# main-v4.net
KiCad netlist of a schematic drawn in EAGLE
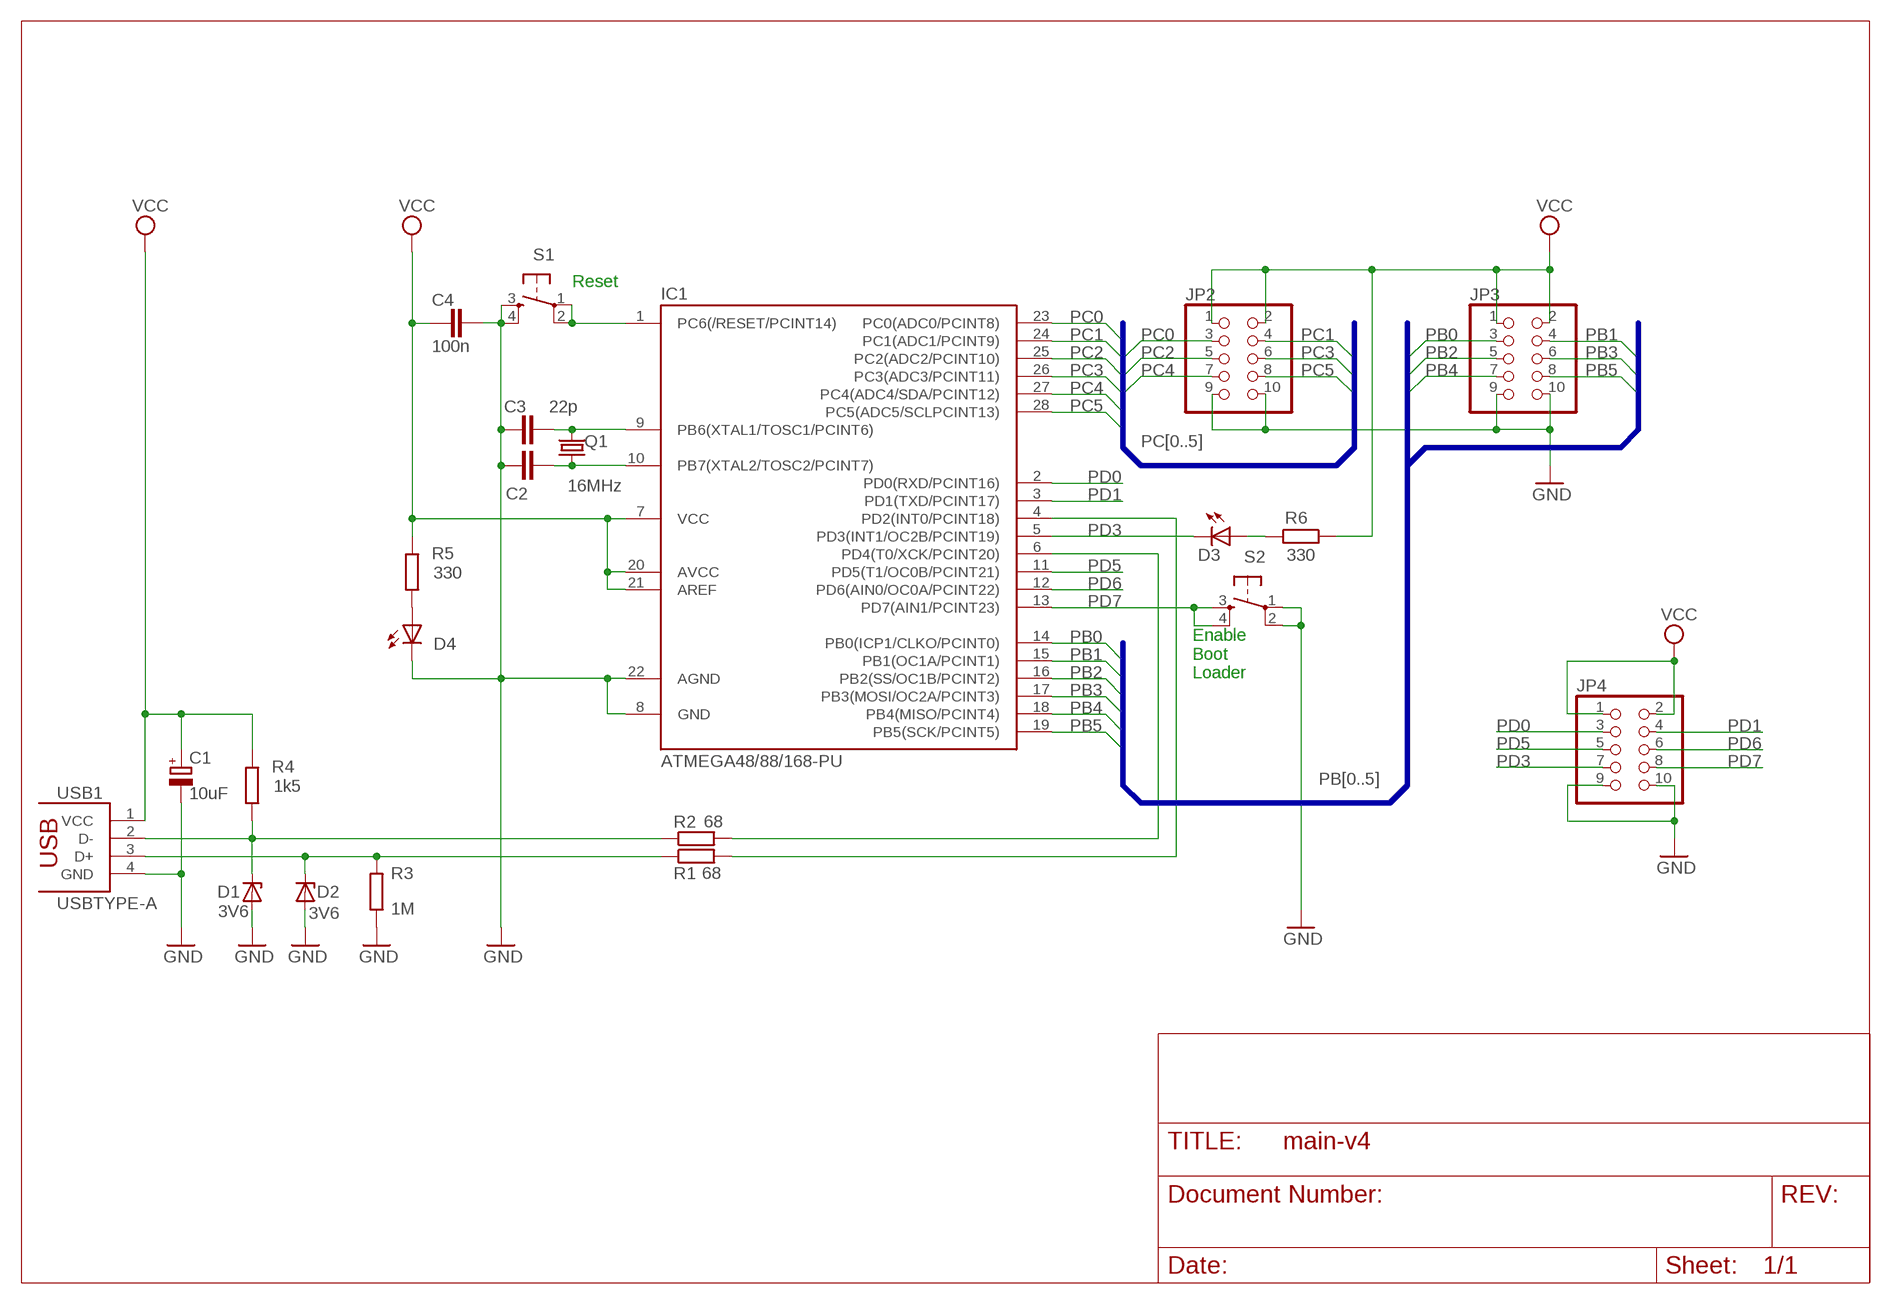
[diagram p0: schematic, sheet 1]

(export (version "E")
  (design (tool "Eeschema 10.0.6"))
  (components
    (comp (ref "C1")
      (value "10uF")
      (footprint "eagle-import:E2,5-6E")
      (libsource (lib "eagle-import") (part "CPOL-EUE2,5-6E"))
    )
    (comp (ref "C2")
      (value "22p")
      (footprint "eagle-import:C025-024X044")
      (libsource (lib "eagle-import") (part "C-EU025-024X044"))
    )
    (comp (ref "C3")
      (value "22p")
      (footprint "eagle-import:C025-024X044")
      (libsource (lib "eagle-import") (part "C-EU025-024X044"))
    )
    (comp (ref "C4")
      (value "100n")
      (footprint "eagle-import:C050-024X044")
      (libsource (lib "eagle-import") (part "C-EU050-024X044"))
    )
    (comp (ref "D1")
      (value "3V6")
      (footprint "eagle-import:DO34Z7")
      (libsource (lib "eagle-import") (part "ZENER-DIODEDO34-7"))
    )
    (comp (ref "D2")
      (value "3V6")
      (footprint "eagle-import:DO34Z7")
      (libsource (lib "eagle-import") (part "ZENER-DIODEDO34-7"))
    )
    (comp (ref "D3")
      (value "LED3MM")
      (footprint "eagle-import:LED3MM")
      (libsource (lib "eagle-import") (part "LED3MM"))
    )
    (comp (ref "D4")
      (value "LED3MM")
      (footprint "eagle-import:LED3MM")
      (libsource (lib "eagle-import") (part "LED3MM"))
    )
    (comp (ref "IC1")
      (value "ATMEGA48/88/168-PU")
      (footprint "eagle-import:DIL28-3")
      (libsource (lib "eagle-import") (part "ATMEGA48/88/168-PU"))
    )
    (comp (ref "JP2")
      (value "HEADER-2X5")
      (footprint "eagle-import:2X05")
      (libsource (lib "eagle-import") (part "HEADER-2X5"))
    )
    (comp (ref "JP3")
      (value "HEADER-2X5")
      (footprint "eagle-import:2X05")
      (libsource (lib "eagle-import") (part "HEADER-2X5"))
    )
    (comp (ref "JP4")
      (value "HEADER-2X5")
      (footprint "eagle-import:2X05")
      (libsource (lib "eagle-import") (part "HEADER-2X5"))
    )
    (comp (ref "Q1")
      (value "16MHz")
      (footprint "eagle-import:HC49_S")
      (libsource (lib "eagle-import") (part "CRYSTALHC49S"))
    )
    (comp (ref "R1")
      (value "68")
      (footprint "eagle-import:0207_10")
      (libsource (lib "eagle-import") (part "R-EU_0207/10"))
    )
    (comp (ref "R2")
      (value "68")
      (footprint "eagle-import:0207_10")
      (libsource (lib "eagle-import") (part "R-EU_0207/10"))
    )
    (comp (ref "R3")
      (value "1M")
      (footprint "eagle-import:0207_10")
      (libsource (lib "eagle-import") (part "R-EU_0207/10"))
    )
    (comp (ref "R4")
      (value "1k5")
      (footprint "eagle-import:0207_10")
      (libsource (lib "eagle-import") (part "R-EU_0207/10"))
    )
    (comp (ref "R5")
      (value "330")
      (footprint "eagle-import:0207_10")
      (libsource (lib "eagle-import") (part "R-EU_0207/10"))
    )
    (comp (ref "R6")
      (value "330")
      (footprint "eagle-import:0207_10")
      (libsource (lib "eagle-import") (part "R-EU_0207/10"))
    )
    (comp (ref "S1")
      (value "DTS-6")
      (footprint "eagle-import:DTS-6")
      (libsource (lib "eagle-import") (part "DTS-6"))
    )
    (comp (ref "S2")
      (value "DTS-6")
      (footprint "eagle-import:DTS-6")
      (libsource (lib "eagle-import") (part "DTS-6"))
    )
    (comp (ref "USB1")
      (value "USBTYPE-A")
      (footprint "eagle-import:USBTYPE-A")
      (libsource (lib "eagle-import") (part "USBTYPE-A"))
    )
  )
  (nets
    (net (code "1") (name "/PB0") (class "Default")
      (node (ref "IC1") (pin "14") (pinfunction "PB0(ICP1/CLKO/PCINT0)_14") (pintype "bidirectional"))
      (node (ref "JP3") (pin "3") (pinfunction "3_3") (pintype "passive"))
    )
    (net (code "2") (name "/PB1") (class "Default")
      (node (ref "IC1") (pin "15") (pinfunction "PB1(OC1A/PCINT1)_15") (pintype "bidirectional"))
      (node (ref "JP3") (pin "4") (pinfunction "4_4") (pintype "passive"))
    )
    (net (code "3") (name "/PB2") (class "Default")
      (node (ref "IC1") (pin "16") (pinfunction "PB2(SS/OC1B/PCINT2)_16") (pintype "bidirectional"))
      (node (ref "JP3") (pin "5") (pinfunction "5_5") (pintype "passive"))
    )
    (net (code "4") (name "/PB3") (class "Default")
      (node (ref "IC1") (pin "17") (pinfunction "PB3(MOSI/OC2A/PCINT3)_17") (pintype "bidirectional"))
      (node (ref "JP3") (pin "6") (pinfunction "6_6") (pintype "passive"))
    )
    (net (code "5") (name "/PB4") (class "Default")
      (node (ref "IC1") (pin "18") (pinfunction "PB4(MISO/PCINT4)_18") (pintype "bidirectional"))
      (node (ref "JP3") (pin "7") (pinfunction "7_7") (pintype "passive"))
    )
    (net (code "6") (name "/PB5") (class "Default")
      (node (ref "IC1") (pin "19") (pinfunction "PB5(SCK/PCINT5)_19") (pintype "bidirectional"))
      (node (ref "JP3") (pin "8") (pinfunction "8_8") (pintype "passive"))
    )
    (net (code "8") (name "/PC0") (class "Default")
      (node (ref "IC1") (pin "23") (pinfunction "PC0(ADC0/PCINT8)_23") (pintype "bidirectional"))
      (node (ref "JP2") (pin "3") (pinfunction "3_3") (pintype "passive"))
    )
    (net (code "9") (name "/PC1") (class "Default")
      (node (ref "IC1") (pin "24") (pinfunction "PC1(ADC1/PCINT9)_24") (pintype "bidirectional"))
      (node (ref "JP2") (pin "4") (pinfunction "4_4") (pintype "passive"))
    )
    (net (code "10") (name "/PC2") (class "Default")
      (node (ref "IC1") (pin "25") (pinfunction "PC2(ADC2/PCINT10)_25") (pintype "bidirectional"))
      (node (ref "JP2") (pin "5") (pinfunction "5_5") (pintype "passive"))
    )
    (net (code "11") (name "/PC3") (class "Default")
      (node (ref "IC1") (pin "26") (pinfunction "PC3(ADC3/PCINT11)_26") (pintype "bidirectional"))
      (node (ref "JP2") (pin "6") (pinfunction "6_6") (pintype "passive"))
    )
    (net (code "12") (name "/PC4") (class "Default")
      (node (ref "IC1") (pin "27") (pinfunction "PC4(ADC4/SDA/PCINT12)_27") (pintype "bidirectional"))
      (node (ref "JP2") (pin "7") (pinfunction "7_7") (pintype "passive"))
    )
    (net (code "13") (name "/PC5") (class "Default")
      (node (ref "IC1") (pin "28") (pinfunction "PC5(ADC5/SCLPCINT13)_28") (pintype "bidirectional"))
      (node (ref "JP2") (pin "8") (pinfunction "8_8") (pintype "passive"))
    )
    (net (code "15") (name "/PD0") (class "Default")
      (node (ref "IC1") (pin "2") (pinfunction "PD0(RXD/PCINT16)_2") (pintype "bidirectional"))
      (node (ref "JP4") (pin "3") (pinfunction "3_3") (pintype "passive"))
    )
    (net (code "16") (name "/PD1") (class "Default")
      (node (ref "IC1") (pin "3") (pinfunction "PD1(TXD/PCINT17)_3") (pintype "bidirectional"))
      (node (ref "JP4") (pin "4") (pinfunction "4_4") (pintype "passive"))
    )
    (net (code "17") (name "/PD3") (class "Default")
      (node (ref "D3") (pin "K") (pinfunction "C_K") (pintype "passive"))
      (node (ref "IC1") (pin "5") (pinfunction "PD3(INT1/OC2B/PCINT19)_5") (pintype "bidirectional"))
      (node (ref "JP4") (pin "7") (pinfunction "7_7") (pintype "passive"))
    )
    (net (code "18") (name "/PD5") (class "Default")
      (node (ref "IC1") (pin "11") (pinfunction "PD5(T1/OC0B/PCINT21)_11") (pintype "bidirectional"))
      (node (ref "JP4") (pin "5") (pinfunction "5_5") (pintype "passive"))
    )
    (net (code "19") (name "/PD6") (class "Default")
      (node (ref "IC1") (pin "12") (pinfunction "PD6(AIN0/OC0A/PCINT22)_12") (pintype "bidirectional"))
      (node (ref "JP4") (pin "6") (pinfunction "6_6") (pintype "passive"))
    )
    (net (code "20") (name "/PD7") (class "Default")
      (node (ref "IC1") (pin "13") (pinfunction "PD7(AIN1/PCINT23)_13") (pintype "bidirectional"))
      (node (ref "JP4") (pin "8") (pinfunction "8_8") (pintype "passive"))
      (node (ref "S2") (pin "3") (pinfunction "3_3") (pintype "passive"))
      (node (ref "S2") (pin "4") (pinfunction "4_4") (pintype "passive"))
    )
    (net (code "21") (name "GND") (class "Default")
      (node (ref "C1") (pin "-") (pinfunction "-_-") (pintype "passive"))
      (node (ref "C2") (pin "1") (pinfunction "1_1") (pintype "passive"))
      (node (ref "C3") (pin "1") (pinfunction "1_1") (pintype "passive"))
      (node (ref "C4") (pin "2") (pinfunction "2_2") (pintype "passive"))
      (node (ref "D1") (pin "A") (pinfunction "A_A") (pintype "passive"))
      (node (ref "D2") (pin "A") (pinfunction "A_A") (pintype "passive"))
      (node (ref "D4") (pin "K") (pinfunction "C_K") (pintype "passive"))
      (node (ref "IC1") (pin "22") (pinfunction "AGND_22") (pintype "power_in"))
      (node (ref "IC1") (pin "8") (pinfunction "GND_8") (pintype "power_in"))
      (node (ref "JP2") (pin "10") (pinfunction "10_10") (pintype "passive"))
      (node (ref "JP2") (pin "9") (pinfunction "9_9") (pintype "passive"))
      (node (ref "JP3") (pin "10") (pinfunction "10_10") (pintype "passive"))
      (node (ref "JP3") (pin "9") (pinfunction "9_9") (pintype "passive"))
      (node (ref "JP4") (pin "10") (pinfunction "10_10") (pintype "passive"))
      (node (ref "JP4") (pin "9") (pinfunction "9_9") (pintype "passive"))
      (node (ref "R3") (pin "1") (pinfunction "1_1") (pintype "passive"))
      (node (ref "S1") (pin "3") (pinfunction "3_3") (pintype "passive"))
      (node (ref "S1") (pin "4") (pinfunction "4_4") (pintype "passive"))
      (node (ref "S2") (pin "1") (pinfunction "1_1") (pintype "passive"))
      (node (ref "S2") (pin "2") (pinfunction "2_2") (pintype "passive"))
      (node (ref "USB1") (pin "4") (pinfunction "GND_4") (pintype "power_in"))
    )
    (net (code "22") (name "Net-(D3-PadA)") (class "Default")
      (node (ref "D3") (pin "A") (pinfunction "A_A") (pintype "passive"))
      (node (ref "R6") (pin "2") (pinfunction "2_2") (pintype "passive"))
    )
    (net (code "23") (name "Net-(D4-PadA)") (class "Default")
      (node (ref "D4") (pin "A") (pinfunction "A_A") (pintype "passive"))
      (node (ref "R5") (pin "2") (pinfunction "2_2") (pintype "passive"))
    )
    (net (code "24") (name "Net-(IC1-PB6(XTAL1{slash}TOSC1{slash}PCINT6))") (class "Default")
      (node (ref "C3") (pin "2") (pinfunction "2_2") (pintype "passive"))
      (node (ref "IC1") (pin "9") (pinfunction "PB6(XTAL1/TOSC1/PCINT6)_9") (pintype "bidirectional"))
      (node (ref "Q1") (pin "2") (pinfunction "2_2") (pintype "passive"))
    )
    (net (code "25") (name "Net-(IC1-PB7(XTAL2{slash}TOSC2{slash}PCINT7))") (class "Default")
      (node (ref "C2") (pin "2") (pinfunction "2_2") (pintype "passive"))
      (node (ref "IC1") (pin "10") (pinfunction "PB7(XTAL2/TOSC2/PCINT7)_10") (pintype "bidirectional"))
      (node (ref "Q1") (pin "1") (pinfunction "1_1") (pintype "passive"))
    )
    (net (code "26") (name "Net-(IC1-PC6({slash}RESET{slash}PCINT14))") (class "Default")
      (node (ref "IC1") (pin "1") (pinfunction "PC6(/RESET/PCINT14)_1") (pintype "bidirectional"))
      (node (ref "S1") (pin "1") (pinfunction "1_1") (pintype "passive"))
      (node (ref "S1") (pin "2") (pinfunction "2_2") (pintype "passive"))
    )
    (net (code "27") (name "Net-(IC1-PD2(INT0{slash}PCINT18))") (class "Default")
      (node (ref "IC1") (pin "4") (pinfunction "PD2(INT0/PCINT18)_4") (pintype "bidirectional"))
      (node (ref "R1") (pin "2") (pinfunction "2_2") (pintype "passive"))
    )
    (net (code "28") (name "Net-(IC1-PD4(T0{slash}XCK{slash}PCINT20))") (class "Default")
      (node (ref "IC1") (pin "6") (pinfunction "PD4(T0/XCK/PCINT20)_6") (pintype "bidirectional"))
      (node (ref "R2") (pin "2") (pinfunction "2_2") (pintype "passive"))
    )
    (net (code "29") (name "Net-(USB1-D+)") (class "Default")
      (node (ref "D2") (pin "C") (pinfunction "C_C") (pintype "passive"))
      (node (ref "R1") (pin "1") (pinfunction "1_1") (pintype "passive"))
      (node (ref "R3") (pin "2") (pinfunction "2_2") (pintype "passive"))
      (node (ref "USB1") (pin "3") (pinfunction "D+_3") (pintype "bidirectional"))
    )
    (net (code "30") (name "Net-(USB1-D-)") (class "Default")
      (node (ref "D1") (pin "C") (pinfunction "C_C") (pintype "passive"))
      (node (ref "R2") (pin "1") (pinfunction "1_1") (pintype "passive"))
      (node (ref "R4") (pin "2") (pinfunction "2_2") (pintype "passive"))
      (node (ref "USB1") (pin "2") (pinfunction "D-_2") (pintype "bidirectional"))
    )
    (net (code "31") (name "VCC") (class "Default")
      (node (ref "C1") (pin "+") (pinfunction "+_+") (pintype "passive"))
      (node (ref "C4") (pin "1") (pinfunction "1_1") (pintype "passive"))
      (node (ref "IC1") (pin "20") (pinfunction "AVCC_20") (pintype "passive"))
      (node (ref "IC1") (pin "21") (pinfunction "AREF_21") (pintype "passive"))
      (node (ref "IC1") (pin "7") (pinfunction "VCC_7") (pintype "power_in"))
      (node (ref "JP2") (pin "1") (pinfunction "1_1") (pintype "passive"))
      (node (ref "JP2") (pin "2") (pinfunction "2_2") (pintype "passive"))
      (node (ref "JP3") (pin "1") (pinfunction "1_1") (pintype "passive"))
      (node (ref "JP3") (pin "2") (pinfunction "2_2") (pintype "passive"))
      (node (ref "JP4") (pin "1") (pinfunction "1_1") (pintype "passive"))
      (node (ref "JP4") (pin "2") (pinfunction "2_2") (pintype "passive"))
      (node (ref "R4") (pin "1") (pinfunction "1_1") (pintype "passive"))
      (node (ref "R5") (pin "1") (pinfunction "1_1") (pintype "passive"))
      (node (ref "R6") (pin "1") (pinfunction "1_1") (pintype "passive"))
      (node (ref "USB1") (pin "1") (pinfunction "VCC_1") (pintype "power_in"))
    )
  )
)
